# DS3231.net
KiCad netlist of a schematic drawn in EAGLE
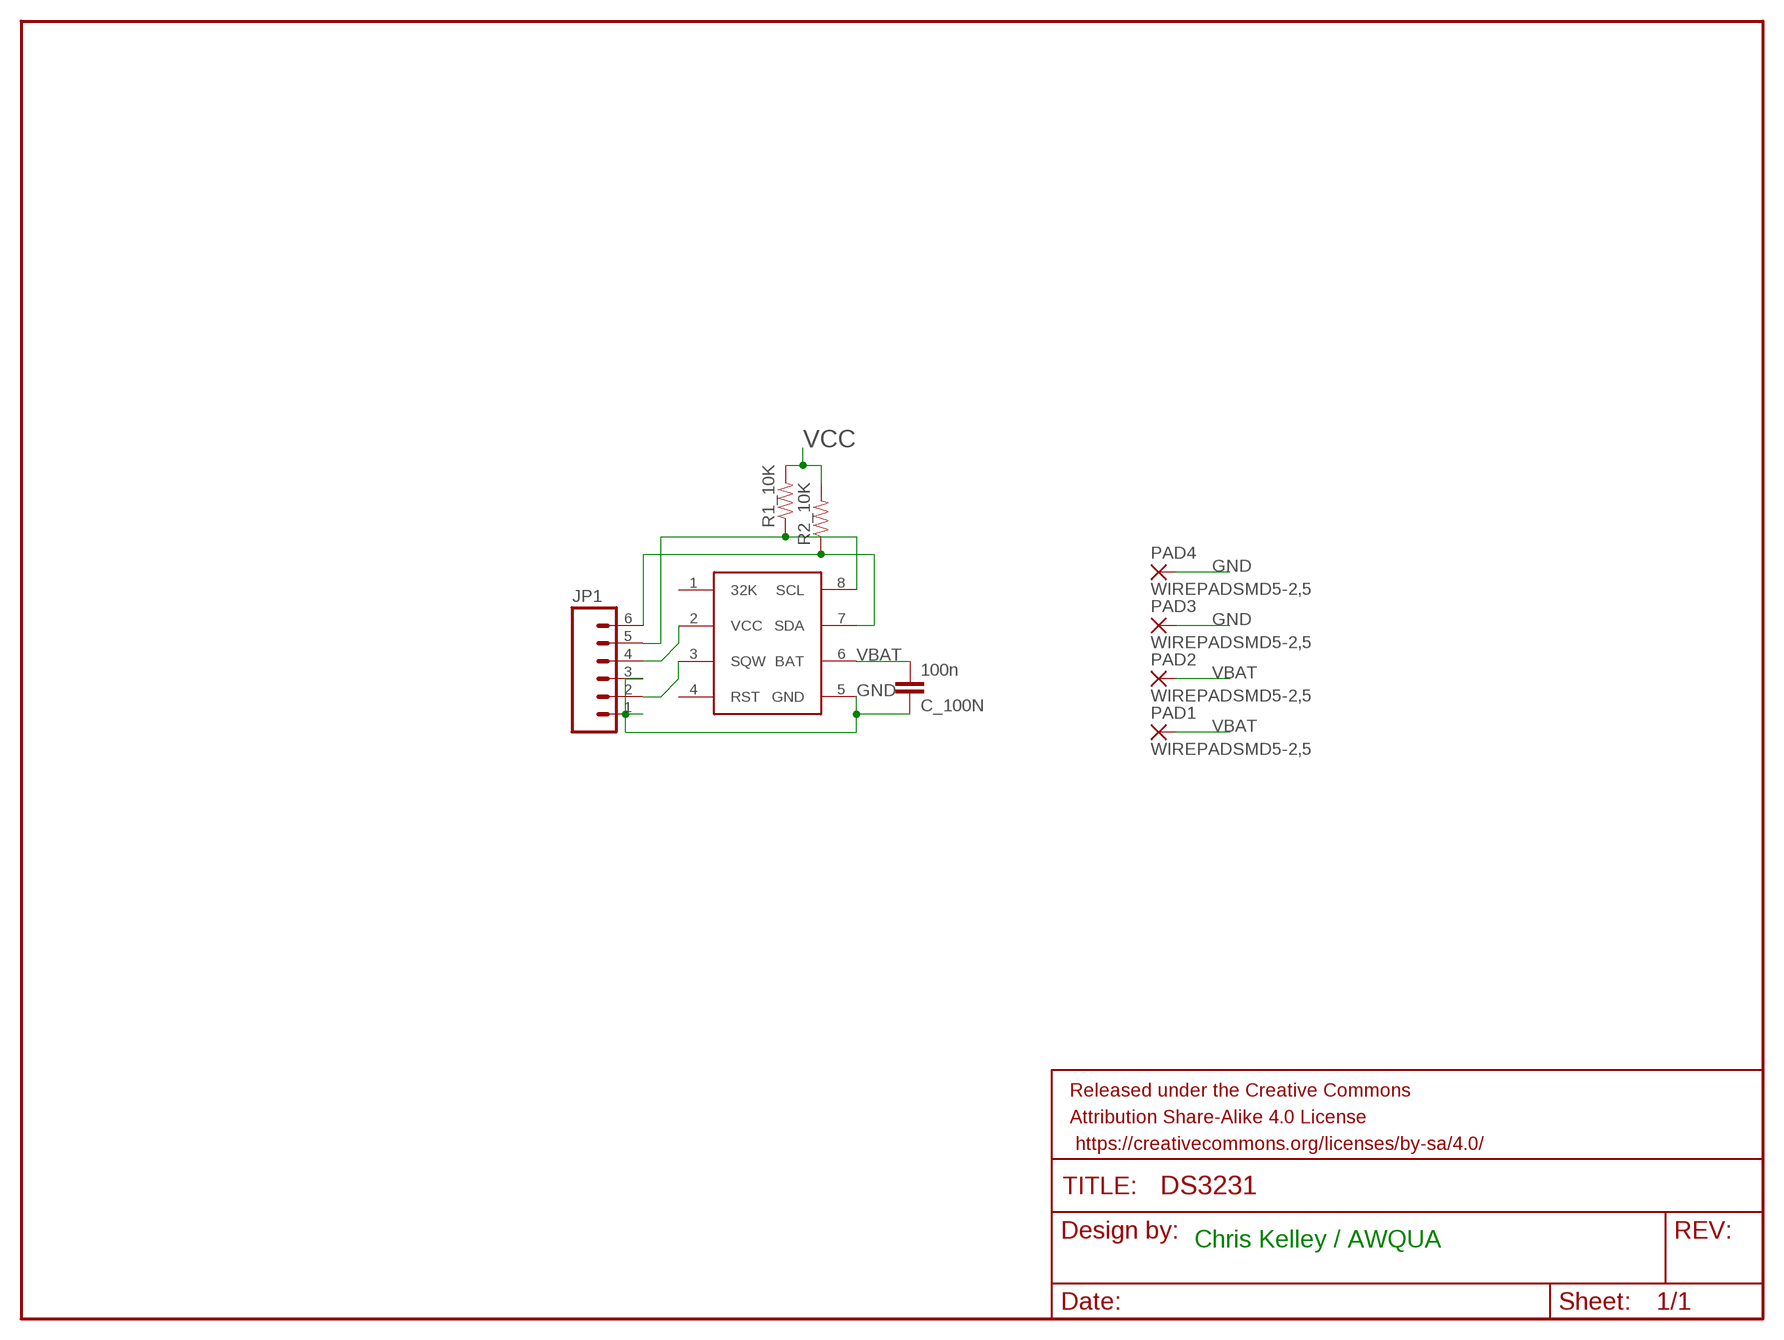
[diagram p0: schematic, sheet 1]

(export (version "E")
  (design (tool "Eeschema 10.0.6"))
  (components
    (comp (ref "C_100N")
      (value "100n")
      (footprint "eagle-import:0603-CAP")
      (libsource (lib "eagle-import") (part "CAP0603-CAP"))
    )
    (comp (ref "DS3231")
      (value "DS3231M")
      (footprint "eagle-import:DS3231M")
      (libsource (lib "eagle-import") (part "DS3231M"))
    )
    (comp (ref "FRAME1")
      (value "FRAME-LETTER")
      (footprint "eagle-import:CREATIVE_COMMONS")
      (libsource (lib "eagle-import") (part "FRAME-LETTER"))
    )
    (comp (ref "JP1")
      (value "M06SILK_FEMALE_PTH")
      (footprint "eagle-import:1X06")
      (libsource (lib "eagle-import") (part "M06SILK_FEMALE_PTH"))
    )
    (comp (ref "PAD1")
      (value "WIREPADSMD5-2,5")
      (footprint "eagle-import:5-2,5")
      (libsource (lib "eagle-import") (part "WIREPADSMD5-2,5"))
    )
    (comp (ref "PAD2")
      (value "WIREPADSMD5-2,5")
      (footprint "eagle-import:5-2,5")
      (libsource (lib "eagle-import") (part "WIREPADSMD5-2,5"))
    )
    (comp (ref "PAD3")
      (value "WIREPADSMD5-2,5")
      (footprint "eagle-import:5-2,5")
      (libsource (lib "eagle-import") (part "WIREPADSMD5-2,5"))
    )
    (comp (ref "PAD4")
      (value "WIREPADSMD5-2,5")
      (footprint "eagle-import:5-2,5")
      (libsource (lib "eagle-import") (part "WIREPADSMD5-2,5"))
    )
    (comp (ref "R1_10K")
      (value "RESISTOR0603-RES")
      (footprint "eagle-import:0603-RES")
      (libsource (lib "eagle-import") (part "RESISTOR0603-RES"))
    )
    (comp (ref "R2_10K")
      (value "RESISTOR0603-RES")
      (footprint "eagle-import:0603-RES")
      (libsource (lib "eagle-import") (part "RESISTOR0603-RES"))
    )
  )
  (nets
    (net (code "1") (name "/GND") (class "Default")
      (node (ref "C_100N") (pin "1") (pinfunction "1_1") (pintype "passive"))
      (node (ref "DS3231") (pin "5") (pinfunction "GND_5") (pintype "bidirectional"))
      (node (ref "JP1") (pin "1") (pinfunction "1_1") (pintype "passive"))
      (node (ref "JP1") (pin "3") (pinfunction "3_3") (pintype "passive"))
      (node (ref "PAD3") (pin "1") (pinfunction "P_1") (pintype "passive"))
      (node (ref "PAD4") (pin "1") (pinfunction "P_1") (pintype "passive"))
    )
    (net (code "2") (name "/VBAT") (class "Default")
      (node (ref "C_100N") (pin "2") (pinfunction "2_2") (pintype "passive"))
      (node (ref "DS3231") (pin "6") (pinfunction "BAT_6") (pintype "bidirectional"))
      (node (ref "PAD1") (pin "1") (pinfunction "P_1") (pintype "passive"))
      (node (ref "PAD2") (pin "1") (pinfunction "P_1") (pintype "passive"))
    )
    (net (code "3") (name "/VCC") (class "Default")
      (node (ref "DS3231") (pin "2") (pinfunction "VCC_2") (pintype "bidirectional"))
      (node (ref "JP1") (pin "4") (pinfunction "4_4") (pintype "passive"))
      (node (ref "R1_10K") (pin "2") (pinfunction "2_2") (pintype "passive"))
      (node (ref "R2_10K") (pin "2") (pinfunction "2_2") (pintype "passive"))
    )
    (net (code "4") (name "Net-(DS3231-SCL)") (class "Default")
      (node (ref "DS3231") (pin "8") (pinfunction "SCL_8") (pintype "bidirectional"))
      (node (ref "JP1") (pin "5") (pinfunction "5_5") (pintype "passive"))
      (node (ref "R1_10K") (pin "1") (pinfunction "1_1") (pintype "passive"))
    )
    (net (code "5") (name "Net-(DS3231-SDA)") (class "Default")
      (node (ref "DS3231") (pin "7") (pinfunction "SDA_7") (pintype "bidirectional"))
      (node (ref "JP1") (pin "6") (pinfunction "6_6") (pintype "passive"))
      (node (ref "R2_10K") (pin "1") (pinfunction "1_1") (pintype "passive"))
    )
    (net (code "6") (name "Net-(DS3231-SQW)") (class "Default")
      (node (ref "DS3231") (pin "3") (pinfunction "SQW_3") (pintype "bidirectional"))
      (node (ref "JP1") (pin "2") (pinfunction "2_2") (pintype "passive"))
    )
    (net (code "7") (name "unconnected-(DS3231-32K-Pad1)") (class "Default")
      (node (ref "DS3231") (pin "1") (pinfunction "32K_1") (pintype "bidirectional"))
    )
    (net (code "8") (name "unconnected-(DS3231-RST-Pad4)") (class "Default")
      (node (ref "DS3231") (pin "4") (pinfunction "RST_4") (pintype "bidirectional"))
    )
  )
)
